# inductor_test_2v0.net
KiCad netlist of a schematic drawn in EAGLE
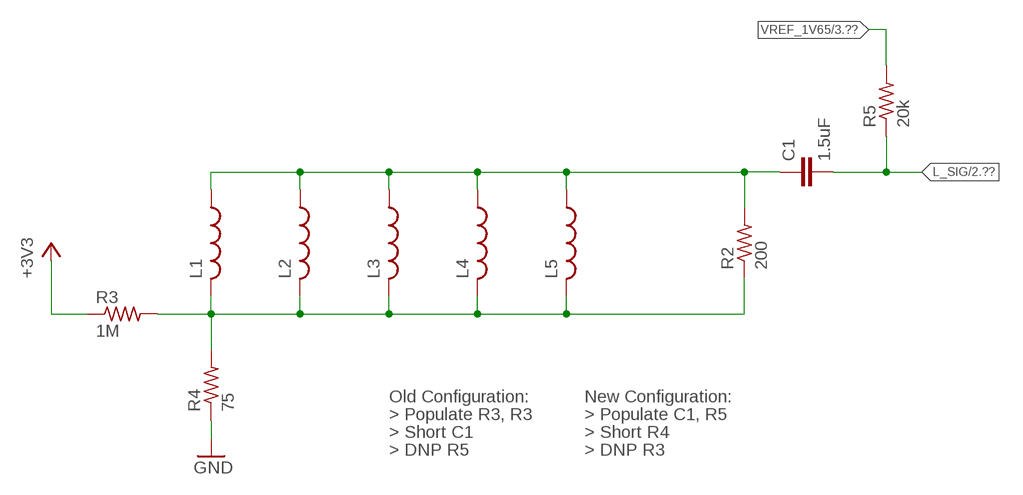
[diagram p0: schematic, sheet 1]
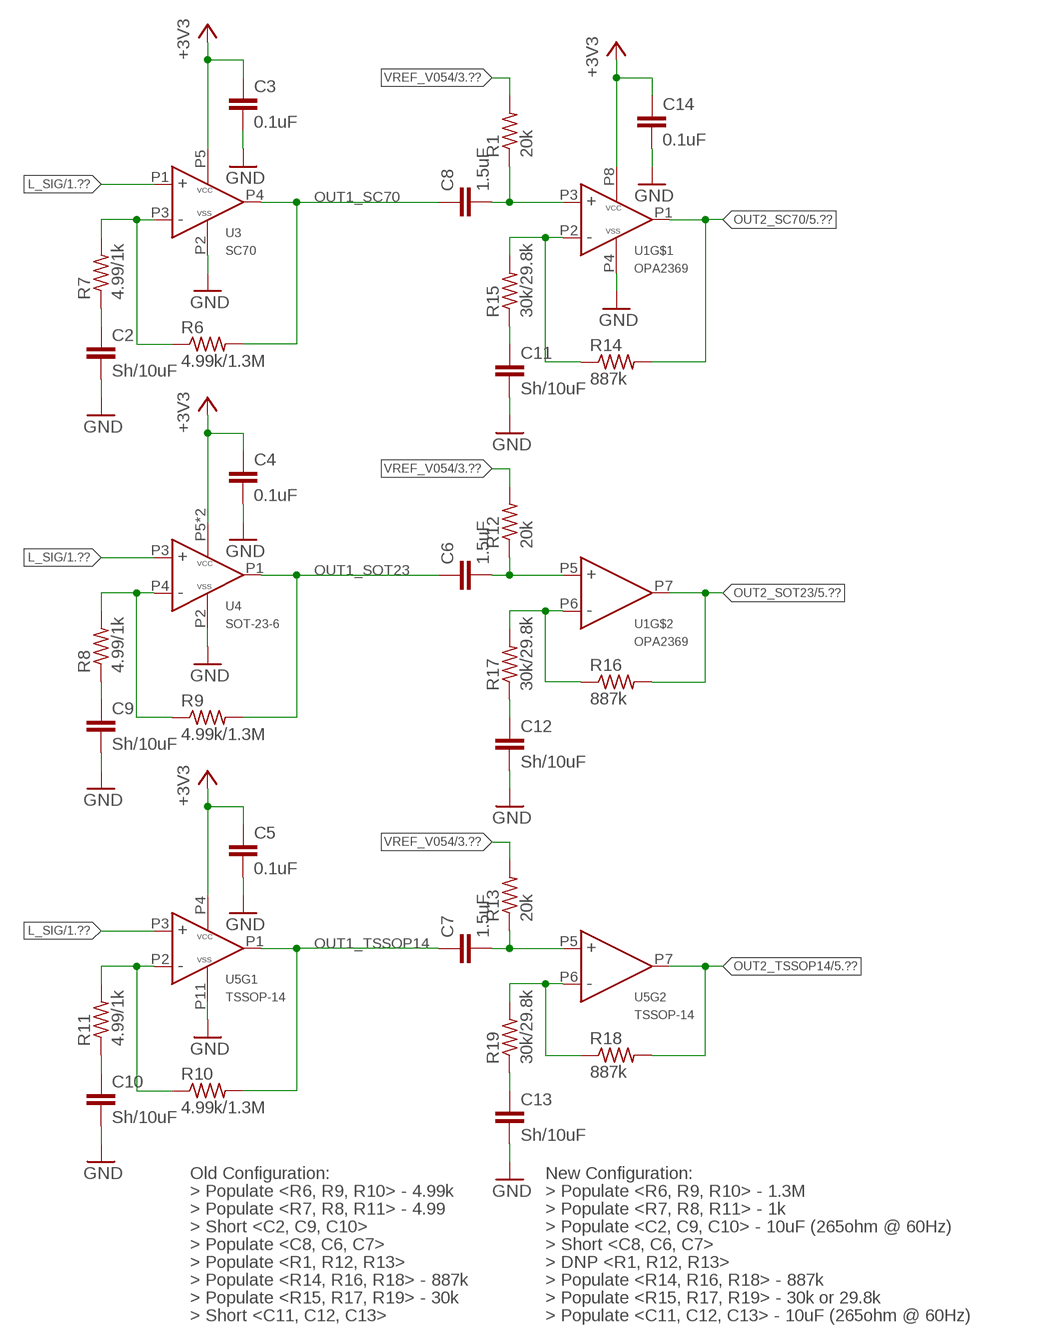
[diagram p1: schematic, sheet 2]
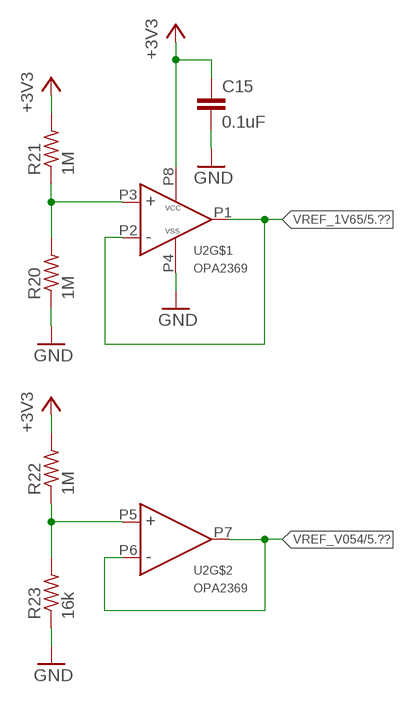
[diagram p2: schematic, sheet 3]
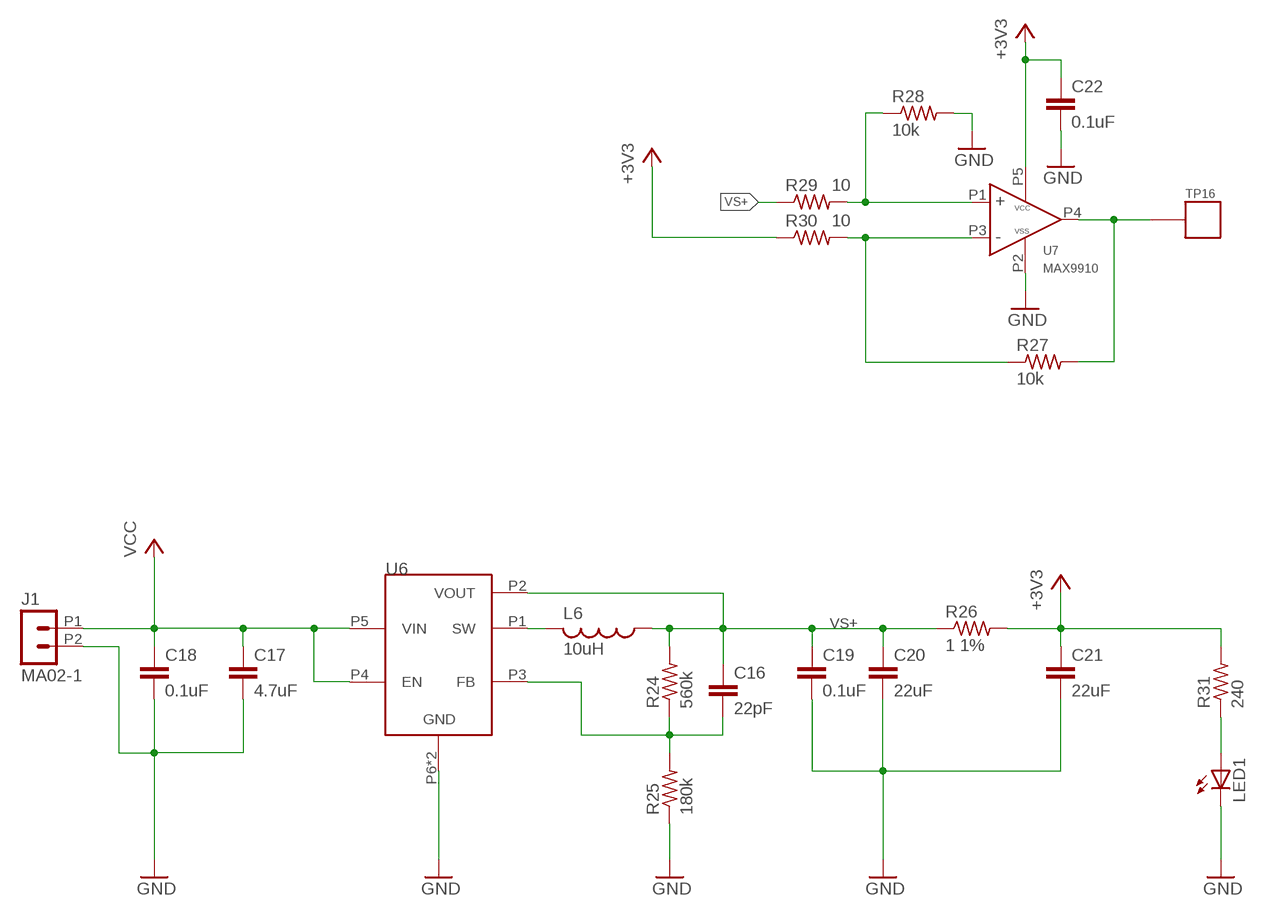
[diagram p3: schematic, sheet 4]
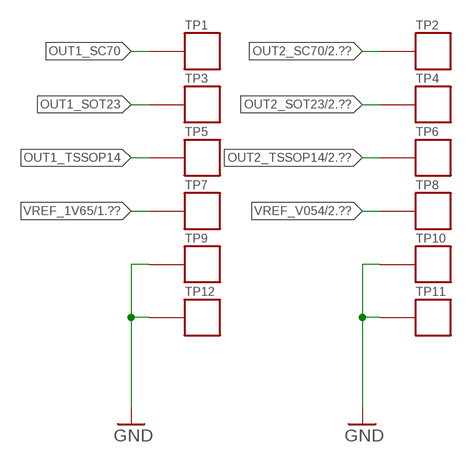
[diagram p4: schematic, sheet 5]

(export (version "E")
  (design (tool "Eeschema 10.0.6"))
  (components
    (comp (ref "C16")
      (value "22pF")
      (footprint "eagle-import:C0402_SM")
      (libsource (lib "eagle-import") (part "C-EUC0402_SM"))
    )
    (comp (ref "C17")
      (value "4.7uF")
      (footprint "eagle-import:C0402_SM")
      (libsource (lib "eagle-import") (part "C-EUC0402_SM"))
    )
    (comp (ref "C18")
      (value "0.1uF")
      (footprint "eagle-import:C0402_SM")
      (libsource (lib "eagle-import") (part "C-EUC0402_SM"))
    )
    (comp (ref "C19")
      (value "0.1uF")
      (footprint "eagle-import:C0402_SM")
      (libsource (lib "eagle-import") (part "C-EUC0402_SM"))
    )
    (comp (ref "C20")
      (value "22uF")
      (footprint "eagle-import:C0603_SM")
      (libsource (lib "eagle-import") (part "C-EUC0603_SM"))
    )
    (comp (ref "C21")
      (value "22uF")
      (footprint "eagle-import:C0603_SM")
      (libsource (lib "eagle-import") (part "C-EUC0603_SM"))
    )
    (comp (ref "C22")
      (value "0.1uF")
      (footprint "eagle-import:C0603")
      (libsource (lib "eagle-import") (part "C-EUC0603"))
    )
    (comp (ref "J1")
      (value "MA02-1")
      (footprint "eagle-import:MA02-1_MOLEX-TH")
      (libsource (lib "eagle-import") (part "MA02-1"))
    )
    (comp (ref "L6")
      (value "10uH")
      (footprint "eagle-import:L0805")
      (libsource (lib "eagle-import") (part "L-USL0805"))
    )
    (comp (ref "LED1")
      (value "LED3MM")
      (footprint "eagle-import:LED3MM")
      (libsource (lib "eagle-import") (part "LED3MM"))
    )
    (comp (ref "R24")
      (value "560k")
      (footprint "eagle-import:R0402_SM")
      (libsource (lib "eagle-import") (part "R-US_R0402_SM"))
    )
    (comp (ref "R25")
      (value "180k")
      (footprint "eagle-import:R0402_SM")
      (libsource (lib "eagle-import") (part "R-US_R0402_SM"))
    )
    (comp (ref "R26")
      (value "1 1%")
      (footprint "eagle-import:R0603_SM")
      (libsource (lib "eagle-import") (part "R-US_R0603_SM"))
    )
    (comp (ref "R27")
      (value "10k")
      (footprint "eagle-import:R0603")
      (libsource (lib "eagle-import") (part "R-US_R0603"))
    )
    (comp (ref "R28")
      (value "10k")
      (footprint "eagle-import:R0603")
      (libsource (lib "eagle-import") (part "R-US_R0603"))
    )
    (comp (ref "R29")
      (value "10")
      (footprint "eagle-import:R0603")
      (libsource (lib "eagle-import") (part "R-US_R0603"))
    )
    (comp (ref "R30")
      (value "10")
      (footprint "eagle-import:R0603")
      (libsource (lib "eagle-import") (part "R-US_R0603"))
    )
    (comp (ref "R31")
      (value "240")
      (footprint "eagle-import:R0603")
      (libsource (lib "eagle-import") (part "R-US_R0603"))
    )
    (comp (ref "TP16")
      (value "TP_MULT")
      (footprint "eagle-import:TP_MULT")
      (libsource (lib "eagle-import") (part "TP_MULT"))
    )
    (comp (ref "U6")
      (value "TPS62122")
      (footprint "eagle-import:WDFN-6")
      (libsource (lib "eagle-import") (part "TPS62122"))
    )
    (comp (ref "U7")
      (value "MAX9910")
      (footprint "eagle-import:SC70-5")
      (libsource (lib "eagle-import") (part "MAX9910"))
    )
    (comp (ref "C15")
      (value "0.1uF")
      (footprint "eagle-import:C0402")
      (libsource (lib "eagle-import") (part "C-EUC0402"))
    )
    (comp (ref "R20")
      (value "1M")
      (footprint "eagle-import:R0402")
      (libsource (lib "eagle-import") (part "R-US_R0402"))
    )
    (comp (ref "R21")
      (value "1M")
      (footprint "eagle-import:R0402")
      (libsource (lib "eagle-import") (part "R-US_R0402"))
    )
    (comp (ref "R22")
      (value "1M")
      (footprint "eagle-import:R0402")
      (libsource (lib "eagle-import") (part "R-US_R0402"))
    )
    (comp (ref "R23")
      (value "16k")
      (footprint "eagle-import:R0402")
      (libsource (lib "eagle-import") (part "R-US_R0402"))
    )
    (comp (ref "U2")
      (value "OPA2369")
      (footprint "eagle-import:SOT-23-8")
      (libsource (lib "eagle-import") (part "OPA2369"))
    )
    (comp (ref "TP1")
      (value "TP_MULT")
      (footprint "eagle-import:TP_MULT")
      (libsource (lib "eagle-import") (part "TP_MULT"))
    )
    (comp (ref "TP2")
      (value "TP_MULT")
      (footprint "eagle-import:TP_MULT")
      (libsource (lib "eagle-import") (part "TP_MULT"))
    )
    (comp (ref "TP3")
      (value "TP_MULT")
      (footprint "eagle-import:TP_MULT")
      (libsource (lib "eagle-import") (part "TP_MULT"))
    )
    (comp (ref "TP4")
      (value "TP_MULT")
      (footprint "eagle-import:TP_MULT")
      (libsource (lib "eagle-import") (part "TP_MULT"))
    )
    (comp (ref "TP5")
      (value "TP_MULT")
      (footprint "eagle-import:TP_MULT")
      (libsource (lib "eagle-import") (part "TP_MULT"))
    )
    (comp (ref "TP6")
      (value "TP_MULT")
      (footprint "eagle-import:TP_MULT")
      (libsource (lib "eagle-import") (part "TP_MULT"))
    )
    (comp (ref "TP7")
      (value "TP_MULT")
      (footprint "eagle-import:TP_MULT")
      (libsource (lib "eagle-import") (part "TP_MULT"))
    )
    (comp (ref "TP8")
      (value "TP_MULT")
      (footprint "eagle-import:TP_MULT")
      (libsource (lib "eagle-import") (part "TP_MULT"))
    )
    (comp (ref "TP9")
      (value "TP_MULT")
      (footprint "eagle-import:TP_MULT")
      (libsource (lib "eagle-import") (part "TP_MULT"))
    )
    (comp (ref "TP10")
      (value "TP_MULT")
      (footprint "eagle-import:TP_MULT")
      (libsource (lib "eagle-import") (part "TP_MULT"))
    )
    (comp (ref "TP11")
      (value "TP_MULT")
      (footprint "eagle-import:TP_MULT")
      (libsource (lib "eagle-import") (part "TP_MULT"))
    )
    (comp (ref "TP12")
      (value "TP_MULT")
      (footprint "eagle-import:TP_MULT")
      (libsource (lib "eagle-import") (part "TP_MULT"))
    )
    (comp (ref "C2")
      (value "Sh/10uF")
      (footprint "eagle-import:C0402")
      (libsource (lib "eagle-import") (part "C-EUC0402"))
    )
    (comp (ref "C3")
      (value "0.1uF")
      (footprint "eagle-import:C0402")
      (libsource (lib "eagle-import") (part "C-EUC0402"))
    )
    (comp (ref "C4")
      (value "0.1uF")
      (footprint "eagle-import:C0402")
      (libsource (lib "eagle-import") (part "C-EUC0402"))
    )
    (comp (ref "C5")
      (value "0.1uF")
      (footprint "eagle-import:C0402")
      (libsource (lib "eagle-import") (part "C-EUC0402"))
    )
    (comp (ref "C6")
      (value "1.5uF")
      (footprint "eagle-import:C0402")
      (libsource (lib "eagle-import") (part "C-EUC0402"))
    )
    (comp (ref "C7")
      (value "1.5uF")
      (footprint "eagle-import:C0402")
      (libsource (lib "eagle-import") (part "C-EUC0402"))
    )
    (comp (ref "C8")
      (value "1.5uF")
      (footprint "eagle-import:C0402")
      (libsource (lib "eagle-import") (part "C-EUC0402"))
    )
    (comp (ref "C9")
      (value "Sh/10uF")
      (footprint "eagle-import:C0402")
      (libsource (lib "eagle-import") (part "C-EUC0402"))
    )
    (comp (ref "C10")
      (value "Sh/10uF")
      (footprint "eagle-import:C0402")
      (libsource (lib "eagle-import") (part "C-EUC0402"))
    )
    (comp (ref "C11")
      (value "Sh/10uF")
      (footprint "eagle-import:C0402")
      (libsource (lib "eagle-import") (part "C-EUC0402"))
    )
    (comp (ref "C12")
      (value "Sh/10uF")
      (footprint "eagle-import:C0402")
      (libsource (lib "eagle-import") (part "C-EUC0402"))
    )
    (comp (ref "C13")
      (value "Sh/10uF")
      (footprint "eagle-import:C0402")
      (libsource (lib "eagle-import") (part "C-EUC0402"))
    )
    (comp (ref "C14")
      (value "0.1uF")
      (footprint "eagle-import:C0402")
      (libsource (lib "eagle-import") (part "C-EUC0402"))
    )
    (comp (ref "R1")
      (value "20k")
      (footprint "eagle-import:R0402")
      (libsource (lib "eagle-import") (part "R-US_R0402"))
    )
    (comp (ref "R6")
      (value "4.99k/1.3M")
      (footprint "eagle-import:R0402")
      (libsource (lib "eagle-import") (part "R-US_R0402"))
    )
    (comp (ref "R7")
      (value "4.99/1k")
      (footprint "eagle-import:R0402")
      (libsource (lib "eagle-import") (part "R-US_R0402"))
    )
    (comp (ref "R8")
      (value "4.99/1k")
      (footprint "eagle-import:R0402")
      (libsource (lib "eagle-import") (part "R-US_R0402"))
    )
    (comp (ref "R9")
      (value "4.99k/1.3M")
      (footprint "eagle-import:R0402")
      (libsource (lib "eagle-import") (part "R-US_R0402"))
    )
    (comp (ref "R10")
      (value "4.99k/1.3M")
      (footprint "eagle-import:R0402")
      (libsource (lib "eagle-import") (part "R-US_R0402"))
    )
    (comp (ref "R11")
      (value "4.99/1k")
      (footprint "eagle-import:R0402")
      (libsource (lib "eagle-import") (part "R-US_R0402"))
    )
    (comp (ref "R12")
      (value "20k")
      (footprint "eagle-import:R0402")
      (libsource (lib "eagle-import") (part "R-US_R0402"))
    )
    (comp (ref "R13")
      (value "20k")
      (footprint "eagle-import:R0402")
      (libsource (lib "eagle-import") (part "R-US_R0402"))
    )
    (comp (ref "R14")
      (value "887k")
      (footprint "eagle-import:R0402")
      (libsource (lib "eagle-import") (part "R-US_R0402"))
    )
    (comp (ref "R15")
      (value "30k/29.8k")
      (footprint "eagle-import:R0402")
      (libsource (lib "eagle-import") (part "R-US_R0402"))
    )
    (comp (ref "R16")
      (value "887k")
      (footprint "eagle-import:R0402")
      (libsource (lib "eagle-import") (part "R-US_R0402"))
    )
    (comp (ref "R17")
      (value "30k/29.8k")
      (footprint "eagle-import:R0402")
      (libsource (lib "eagle-import") (part "R-US_R0402"))
    )
    (comp (ref "R18")
      (value "887k")
      (footprint "eagle-import:R0402")
      (libsource (lib "eagle-import") (part "R-US_R0402"))
    )
    (comp (ref "R19")
      (value "30k/29.8k")
      (footprint "eagle-import:R0402")
      (libsource (lib "eagle-import") (part "R-US_R0402"))
    )
    (comp (ref "U1")
      (value "OPA2369")
      (footprint "eagle-import:SOT-23-8")
      (libsource (lib "eagle-import") (part "OPA2369"))
    )
    (comp (ref "U3")
      (value "SC70")
      (footprint "eagle-import:SC70-5")
      (fields (field (name "DIGIKEY") "296-22191-1-ND"))
      (libsource (lib "eagle-import") (part "MCP6V3"))
    )
    (comp (ref "U4")
      (value "SOT-23-6")
      (footprint "eagle-import:SOT-23-6")
      (libsource (lib "eagle-import") (part "MAX4238"))
    )
    (comp (ref "U5")
      (value "TSSOP-14")
      (footprint "eagle-import:TSSOP-14")
      (libsource (lib "eagle-import") (part "LMP2014"))
    )
    (comp (ref "C1")
      (value "1.5uF")
      (footprint "eagle-import:C0402")
      (libsource (lib "eagle-import") (part "C-EUC0402"))
    )
    (comp (ref "L1")
      (value "L-USL0805")
      (footprint "eagle-import:L0805")
      (libsource (lib "eagle-import") (part "L-USL0805"))
    )
    (comp (ref "L2")
      (value "L-USL0805")
      (footprint "eagle-import:L0805")
      (libsource (lib "eagle-import") (part "L-USL0805"))
    )
    (comp (ref "L3")
      (value "L-USL0805")
      (footprint "eagle-import:L0805")
      (libsource (lib "eagle-import") (part "L-USL0805"))
    )
    (comp (ref "L4")
      (value "L-USL0805")
      (footprint "eagle-import:L0805")
      (libsource (lib "eagle-import") (part "L-USL0805"))
    )
    (comp (ref "L5")
      (value "L-USL0805")
      (footprint "eagle-import:L0805")
      (libsource (lib "eagle-import") (part "L-USL0805"))
    )
    (comp (ref "R2")
      (value "200")
      (footprint "eagle-import:R0402")
      (libsource (lib "eagle-import") (part "R-US_R0402"))
    )
    (comp (ref "R3")
      (value "1M")
      (footprint "eagle-import:R0402")
      (libsource (lib "eagle-import") (part "R-US_R0402"))
    )
    (comp (ref "R4")
      (value "75")
      (footprint "eagle-import:R0402")
      (libsource (lib "eagle-import") (part "R-US_R0402"))
    )
    (comp (ref "R5")
      (value "20k")
      (footprint "eagle-import:R0402")
      (libsource (lib "eagle-import") (part "R-US_R0402"))
    )
  )
  (nets
    (net (code "1") (name "+3V3") (class "Default")
      (node (ref "C14") (pin "1") (pinfunction "1_1") (pintype "passive"))
      (node (ref "C15") (pin "1") (pinfunction "1_1") (pintype "passive"))
      (node (ref "C21") (pin "1") (pinfunction "1_1") (pintype "passive"))
      (node (ref "C22") (pin "1") (pinfunction "1_1") (pintype "passive"))
      (node (ref "C3") (pin "1") (pinfunction "1_1") (pintype "passive"))
      (node (ref "C4") (pin "1") (pinfunction "1_1") (pintype "passive"))
      (node (ref "C5") (pin "1") (pinfunction "1_1") (pintype "passive"))
      (node (ref "R21") (pin "2") (pinfunction "2_2") (pintype "passive"))
      (node (ref "R22") (pin "2") (pinfunction "2_2") (pintype "passive"))
      (node (ref "R26") (pin "2") (pinfunction "2_2") (pintype "passive"))
      (node (ref "R3") (pin "1") (pinfunction "1_1") (pintype "passive"))
      (node (ref "R30") (pin "1") (pinfunction "1_1") (pintype "passive"))
      (node (ref "R31") (pin "2") (pinfunction "2_2") (pintype "passive"))
      (node (ref "U1") (pin "P8") (pinfunction "VCC_P8") (pintype "bidirectional"))
      (node (ref "U2") (pin "P8") (pinfunction "VCC_P8") (pintype "bidirectional"))
      (node (ref "U3") (pin "P5") (pinfunction "VCC_P5") (pintype "bidirectional"))
      (node (ref "U4") (pin "P5") (pinfunction "VCC_P5") (pintype "bidirectional"))
      (node (ref "U4") (pin "P6") (pinfunction "VCC_P6") (pintype "bidirectional"))
      (node (ref "U5") (pin "P4") (pinfunction "VCC_P4") (pintype "bidirectional"))
      (node (ref "U7") (pin "P5") (pinfunction "VCC_P5") (pintype "bidirectional"))
    )
    (net (code "2") (name "GND") (class "Default")
      (node (ref "C10") (pin "2") (pinfunction "2_2") (pintype "passive"))
      (node (ref "C11") (pin "2") (pinfunction "2_2") (pintype "passive"))
      (node (ref "C12") (pin "2") (pinfunction "2_2") (pintype "passive"))
      (node (ref "C13") (pin "2") (pinfunction "2_2") (pintype "passive"))
      (node (ref "C14") (pin "2") (pinfunction "2_2") (pintype "passive"))
      (node (ref "C15") (pin "2") (pinfunction "2_2") (pintype "passive"))
      (node (ref "C17") (pin "2") (pinfunction "2_2") (pintype "passive"))
      (node (ref "C18") (pin "2") (pinfunction "2_2") (pintype "passive"))
      (node (ref "C19") (pin "2") (pinfunction "2_2") (pintype "passive"))
      (node (ref "C2") (pin "2") (pinfunction "2_2") (pintype "passive"))
      (node (ref "C20") (pin "2") (pinfunction "2_2") (pintype "passive"))
      (node (ref "C21") (pin "2") (pinfunction "2_2") (pintype "passive"))
      (node (ref "C22") (pin "2") (pinfunction "2_2") (pintype "passive"))
      (node (ref "C3") (pin "2") (pinfunction "2_2") (pintype "passive"))
      (node (ref "C4") (pin "2") (pinfunction "2_2") (pintype "passive"))
      (node (ref "C5") (pin "2") (pinfunction "2_2") (pintype "passive"))
      (node (ref "C9") (pin "2") (pinfunction "2_2") (pintype "passive"))
      (node (ref "J1") (pin "P2") (pinfunction "2_P2") (pintype "passive"))
      (node (ref "LED1") (pin "K") (pinfunction "C_K") (pintype "passive"))
      (node (ref "R20") (pin "1") (pinfunction "1_1") (pintype "passive"))
      (node (ref "R23") (pin "1") (pinfunction "1_1") (pintype "passive"))
      (node (ref "R25") (pin "1") (pinfunction "1_1") (pintype "passive"))
      (node (ref "R28") (pin "2") (pinfunction "2_2") (pintype "passive"))
      (node (ref "R4") (pin "1") (pinfunction "1_1") (pintype "passive"))
      (node (ref "TP10") (pin "P$1") (pinfunction "P$1_P$1") (pintype "bidirectional"))
      (node (ref "TP11") (pin "P$1") (pinfunction "P$1_P$1") (pintype "bidirectional"))
      (node (ref "TP12") (pin "P$1") (pinfunction "P$1_P$1") (pintype "bidirectional"))
      (node (ref "TP9") (pin "P$1") (pinfunction "P$1_P$1") (pintype "bidirectional"))
      (node (ref "U1") (pin "P4") (pinfunction "VSS_P4") (pintype "bidirectional"))
      (node (ref "U2") (pin "P4") (pinfunction "VSS_P4") (pintype "bidirectional"))
      (node (ref "U3") (pin "P2") (pinfunction "VSS_P2") (pintype "bidirectional"))
      (node (ref "U4") (pin "P2") (pinfunction "VSS_P2") (pintype "bidirectional"))
      (node (ref "U5") (pin "P11") (pinfunction "VSS_P11") (pintype "bidirectional"))
      (node (ref "U6") (pin "P6") (pinfunction "GND_P6") (pintype "bidirectional"))
      (node (ref "U6") (pin "PAD") (pinfunction "GND_PAD") (pintype "bidirectional"))
      (node (ref "U7") (pin "P2") (pinfunction "VSS_P2") (pintype "bidirectional"))
    )
    (net (code "3") (name "L_SIG") (class "Default")
      (node (ref "C1") (pin "2") (pinfunction "2_2") (pintype "passive"))
      (node (ref "R5") (pin "1") (pinfunction "1_1") (pintype "passive"))
      (node (ref "U3") (pin "P1") (pinfunction "IN+_P1") (pintype "bidirectional"))
      (node (ref "U4") (pin "P3") (pinfunction "IN+_P3") (pintype "bidirectional"))
      (node (ref "U5") (pin "P3") (pinfunction "IN+_P3") (pintype "bidirectional"))
    )
    (net (code "4") (name "Net-(C1-Pad1)") (class "Default")
      (node (ref "C1") (pin "1") (pinfunction "1_1") (pintype "passive"))
      (node (ref "L1") (pin "1") (pinfunction "1_1") (pintype "passive"))
      (node (ref "L2") (pin "1") (pinfunction "1_1") (pintype "passive"))
      (node (ref "L3") (pin "1") (pinfunction "1_1") (pintype "passive"))
      (node (ref "L4") (pin "1") (pinfunction "1_1") (pintype "passive"))
      (node (ref "L5") (pin "1") (pinfunction "1_1") (pintype "passive"))
      (node (ref "R2") (pin "2") (pinfunction "2_2") (pintype "passive"))
    )
    (net (code "5") (name "Net-(C2-Pad1)") (class "Default")
      (node (ref "C2") (pin "1") (pinfunction "1_1") (pintype "passive"))
      (node (ref "R7") (pin "1") (pinfunction "1_1") (pintype "passive"))
    )
    (net (code "6") (name "Net-(C9-Pad1)") (class "Default")
      (node (ref "C9") (pin "1") (pinfunction "1_1") (pintype "passive"))
      (node (ref "R8") (pin "1") (pinfunction "1_1") (pintype "passive"))
    )
    (net (code "7") (name "Net-(C10-Pad1)") (class "Default")
      (node (ref "C10") (pin "1") (pinfunction "1_1") (pintype "passive"))
      (node (ref "R11") (pin "1") (pinfunction "1_1") (pintype "passive"))
    )
    (net (code "8") (name "Net-(C11-Pad1)") (class "Default")
      (node (ref "C11") (pin "1") (pinfunction "1_1") (pintype "passive"))
      (node (ref "R15") (pin "1") (pinfunction "1_1") (pintype "passive"))
    )
    (net (code "9") (name "Net-(C12-Pad1)") (class "Default")
      (node (ref "C12") (pin "1") (pinfunction "1_1") (pintype "passive"))
      (node (ref "R17") (pin "1") (pinfunction "1_1") (pintype "passive"))
    )
    (net (code "10") (name "Net-(C13-Pad1)") (class "Default")
      (node (ref "C13") (pin "1") (pinfunction "1_1") (pintype "passive"))
      (node (ref "R19") (pin "1") (pinfunction "1_1") (pintype "passive"))
    )
    (net (code "11") (name "Net-(L1-Pad2)") (class "Default")
      (node (ref "L1") (pin "2") (pinfunction "2_2") (pintype "passive"))
      (node (ref "L2") (pin "2") (pinfunction "2_2") (pintype "passive"))
      (node (ref "L3") (pin "2") (pinfunction "2_2") (pintype "passive"))
      (node (ref "L4") (pin "2") (pinfunction "2_2") (pintype "passive"))
      (node (ref "L5") (pin "2") (pinfunction "2_2") (pintype "passive"))
      (node (ref "R2") (pin "1") (pinfunction "1_1") (pintype "passive"))
      (node (ref "R3") (pin "2") (pinfunction "2_2") (pintype "passive"))
      (node (ref "R4") (pin "2") (pinfunction "2_2") (pintype "passive"))
    )
    (net (code "12") (name "Net-(LED1-PadA)") (class "Default")
      (node (ref "LED1") (pin "A") (pinfunction "A_A") (pintype "passive"))
      (node (ref "R31") (pin "1") (pinfunction "1_1") (pintype "passive"))
    )
    (net (code "13") (name "Net-(U1A-IN+)") (class "Default")
      (node (ref "C8") (pin "2") (pinfunction "2_2") (pintype "passive"))
      (node (ref "R1") (pin "1") (pinfunction "1_1") (pintype "passive"))
      (node (ref "U1") (pin "P3") (pinfunction "IN+_P3") (pintype "bidirectional"))
    )
    (net (code "14") (name "Net-(U1A-IN-)") (class "Default")
      (node (ref "R14") (pin "1") (pinfunction "1_1") (pintype "passive"))
      (node (ref "R15") (pin "2") (pinfunction "2_2") (pintype "passive"))
      (node (ref "U1") (pin "P2") (pinfunction "IN-_P2") (pintype "bidirectional"))
    )
    (net (code "15") (name "Net-(U1B-IN+)") (class "Default")
      (node (ref "C6") (pin "2") (pinfunction "2_2") (pintype "passive"))
      (node (ref "R12") (pin "1") (pinfunction "1_1") (pintype "passive"))
      (node (ref "U1") (pin "P5") (pinfunction "IN+_P5") (pintype "bidirectional"))
    )
    (net (code "16") (name "Net-(U1B-IN-)") (class "Default")
      (node (ref "R16") (pin "1") (pinfunction "1_1") (pintype "passive"))
      (node (ref "R17") (pin "2") (pinfunction "2_2") (pintype "passive"))
      (node (ref "U1") (pin "P6") (pinfunction "IN-_P6") (pintype "bidirectional"))
    )
    (net (code "17") (name "Net-(U2A-IN+)") (class "Default")
      (node (ref "R20") (pin "2") (pinfunction "2_2") (pintype "passive"))
      (node (ref "R21") (pin "1") (pinfunction "1_1") (pintype "passive"))
      (node (ref "U2") (pin "P3") (pinfunction "IN+_P3") (pintype "bidirectional"))
    )
    (net (code "18") (name "Net-(U2B-IN+)") (class "Default")
      (node (ref "R22") (pin "1") (pinfunction "1_1") (pintype "passive"))
      (node (ref "R23") (pin "2") (pinfunction "2_2") (pintype "passive"))
      (node (ref "U2") (pin "P5") (pinfunction "IN+_P5") (pintype "bidirectional"))
    )
    (net (code "19") (name "Net-(U3-IN-)") (class "Default")
      (node (ref "R6") (pin "1") (pinfunction "1_1") (pintype "passive"))
      (node (ref "R7") (pin "2") (pinfunction "2_2") (pintype "passive"))
      (node (ref "U3") (pin "P3") (pinfunction "IN-_P3") (pintype "bidirectional"))
    )
    (net (code "20") (name "Net-(U4-IN-)") (class "Default")
      (node (ref "R8") (pin "2") (pinfunction "2_2") (pintype "passive"))
      (node (ref "R9") (pin "1") (pinfunction "1_1") (pintype "passive"))
      (node (ref "U4") (pin "P4") (pinfunction "IN-_P4") (pintype "bidirectional"))
    )
    (net (code "21") (name "Net-(U5A-IN-)") (class "Default")
      (node (ref "R10") (pin "1") (pinfunction "1_1") (pintype "passive"))
      (node (ref "R11") (pin "2") (pinfunction "2_2") (pintype "passive"))
      (node (ref "U5") (pin "P2") (pinfunction "IN-_P2") (pintype "bidirectional"))
    )
    (net (code "22") (name "Net-(U5B-IN+)") (class "Default")
      (node (ref "C7") (pin "2") (pinfunction "2_2") (pintype "passive"))
      (node (ref "R13") (pin "1") (pinfunction "1_1") (pintype "passive"))
      (node (ref "U5") (pin "P5") (pinfunction "IN+_P5") (pintype "bidirectional"))
    )
    (net (code "23") (name "Net-(U5B-IN-)") (class "Default")
      (node (ref "R18") (pin "1") (pinfunction "1_1") (pintype "passive"))
      (node (ref "R19") (pin "2") (pinfunction "2_2") (pintype "passive"))
      (node (ref "U5") (pin "P6") (pinfunction "IN-_P6") (pintype "bidirectional"))
    )
    (net (code "24") (name "Net-(U6-FB)") (class "Default")
      (node (ref "C16") (pin "2") (pinfunction "2_2") (pintype "passive"))
      (node (ref "R24") (pin "1") (pinfunction "1_1") (pintype "passive"))
      (node (ref "R25") (pin "2") (pinfunction "2_2") (pintype "passive"))
      (node (ref "U6") (pin "P3") (pinfunction "FB_P3") (pintype "bidirectional"))
    )
    (net (code "25") (name "Net-(U6-SW)") (class "Default")
      (node (ref "L6") (pin "2") (pinfunction "2_2") (pintype "passive"))
      (node (ref "U6") (pin "P1") (pinfunction "SW_P1") (pintype "bidirectional"))
    )
    (net (code "26") (name "Net-(U7-IN+)") (class "Default")
      (node (ref "R28") (pin "1") (pinfunction "1_1") (pintype "passive"))
      (node (ref "R29") (pin "2") (pinfunction "2_2") (pintype "passive"))
      (node (ref "U7") (pin "P1") (pinfunction "IN+_P1") (pintype "bidirectional"))
    )
    (net (code "27") (name "Net-(U7-IN-)") (class "Default")
      (node (ref "R27") (pin "1") (pinfunction "1_1") (pintype "passive"))
      (node (ref "R30") (pin "2") (pinfunction "2_2") (pintype "passive"))
      (node (ref "U7") (pin "P3") (pinfunction "IN-_P3") (pintype "bidirectional"))
    )
    (net (code "28") (name "Net-(U7-OUT)") (class "Default")
      (node (ref "R27") (pin "2") (pinfunction "2_2") (pintype "passive"))
      (node (ref "TP16") (pin "P$1") (pinfunction "P$1_P$1") (pintype "bidirectional"))
      (node (ref "U7") (pin "P4") (pinfunction "OUT_P4") (pintype "bidirectional"))
    )
    (net (code "29") (name "OUT1_SC70") (class "Default")
      (node (ref "C8") (pin "1") (pinfunction "1_1") (pintype "passive"))
      (node (ref "R6") (pin "2") (pinfunction "2_2") (pintype "passive"))
      (node (ref "TP1") (pin "P$1") (pinfunction "P$1_P$1") (pintype "bidirectional"))
      (node (ref "U3") (pin "P4") (pinfunction "OUT_P4") (pintype "bidirectional"))
    )
    (net (code "30") (name "OUT1_SOT23") (class "Default")
      (node (ref "C6") (pin "1") (pinfunction "1_1") (pintype "passive"))
      (node (ref "R9") (pin "2") (pinfunction "2_2") (pintype "passive"))
      (node (ref "TP3") (pin "P$1") (pinfunction "P$1_P$1") (pintype "bidirectional"))
      (node (ref "U4") (pin "P1") (pinfunction "OUT_P1") (pintype "bidirectional"))
    )
    (net (code "31") (name "OUT1_TSSOP14") (class "Default")
      (node (ref "C7") (pin "1") (pinfunction "1_1") (pintype "passive"))
      (node (ref "R10") (pin "2") (pinfunction "2_2") (pintype "passive"))
      (node (ref "TP5") (pin "P$1") (pinfunction "P$1_P$1") (pintype "bidirectional"))
      (node (ref "U5") (pin "P1") (pinfunction "OUT_P1") (pintype "bidirectional"))
    )
    (net (code "32") (name "OUT2_SC70") (class "Default")
      (node (ref "R14") (pin "2") (pinfunction "2_2") (pintype "passive"))
      (node (ref "TP2") (pin "P$1") (pinfunction "P$1_P$1") (pintype "bidirectional"))
      (node (ref "U1") (pin "P1") (pinfunction "OUT_P1") (pintype "bidirectional"))
    )
    (net (code "33") (name "OUT2_SOT23") (class "Default")
      (node (ref "R16") (pin "2") (pinfunction "2_2") (pintype "passive"))
      (node (ref "TP4") (pin "P$1") (pinfunction "P$1_P$1") (pintype "bidirectional"))
      (node (ref "U1") (pin "P7") (pinfunction "OUT_P7") (pintype "bidirectional"))
    )
    (net (code "34") (name "OUT2_TSSOP14") (class "Default")
      (node (ref "R18") (pin "2") (pinfunction "2_2") (pintype "passive"))
      (node (ref "TP6") (pin "P$1") (pinfunction "P$1_P$1") (pintype "bidirectional"))
      (node (ref "U5") (pin "P7") (pinfunction "OUT_P7") (pintype "bidirectional"))
    )
    (net (code "35") (name "VCC") (class "Default")
      (node (ref "C17") (pin "1") (pinfunction "1_1") (pintype "passive"))
      (node (ref "C18") (pin "1") (pinfunction "1_1") (pintype "passive"))
      (node (ref "J1") (pin "P1") (pinfunction "1_P1") (pintype "passive"))
      (node (ref "U6") (pin "P4") (pinfunction "EN_P4") (pintype "bidirectional"))
      (node (ref "U6") (pin "P5") (pinfunction "VIN_P5") (pintype "bidirectional"))
    )
    (net (code "36") (name "VREF_1V65") (class "Default")
      (node (ref "R5") (pin "2") (pinfunction "2_2") (pintype "passive"))
      (node (ref "TP7") (pin "P$1") (pinfunction "P$1_P$1") (pintype "bidirectional"))
      (node (ref "U2") (pin "P1") (pinfunction "OUT_P1") (pintype "bidirectional"))
      (node (ref "U2") (pin "P2") (pinfunction "IN-_P2") (pintype "bidirectional"))
    )
    (net (code "37") (name "VREF_V054") (class "Default")
      (node (ref "R1") (pin "2") (pinfunction "2_2") (pintype "passive"))
      (node (ref "R12") (pin "2") (pinfunction "2_2") (pintype "passive"))
      (node (ref "R13") (pin "2") (pinfunction "2_2") (pintype "passive"))
      (node (ref "TP8") (pin "P$1") (pinfunction "P$1_P$1") (pintype "bidirectional"))
      (node (ref "U2") (pin "P6") (pinfunction "IN-_P6") (pintype "bidirectional"))
      (node (ref "U2") (pin "P7") (pinfunction "OUT_P7") (pintype "bidirectional"))
    )
    (net (code "38") (name "VS+") (class "Default")
      (node (ref "C16") (pin "1") (pinfunction "1_1") (pintype "passive"))
      (node (ref "C19") (pin "1") (pinfunction "1_1") (pintype "passive"))
      (node (ref "C20") (pin "1") (pinfunction "1_1") (pintype "passive"))
      (node (ref "L6") (pin "1") (pinfunction "1_1") (pintype "passive"))
      (node (ref "R24") (pin "2") (pinfunction "2_2") (pintype "passive"))
      (node (ref "R26") (pin "1") (pinfunction "1_1") (pintype "passive"))
      (node (ref "R29") (pin "1") (pinfunction "1_1") (pintype "passive"))
      (node (ref "U6") (pin "P2") (pinfunction "VOUT_P2") (pintype "bidirectional"))
    )
  )
)
